# bat_charging.net
KiCad netlist of a schematic drawn in Altium Designer
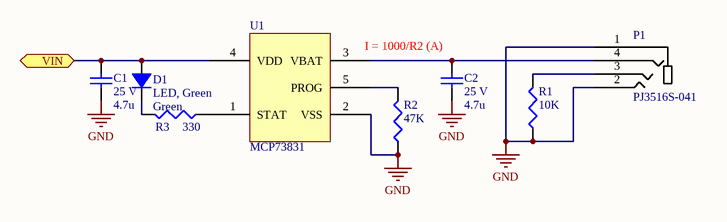
[diagram p0: bat_charging.SchDoc]

(export (version "E")
  (design (tool "Eeschema 10.0.6"))
  (components
    (comp (ref "C1")
      (value "4.7u")
      (footprint "0805")
      (description "Ceramic capacitor, 4.7 uF, 25 V, 0805 package")
      (fields
        (field (name "TOLERANCE") "10%")
        (field (name "VOLTAGE RATED") "25 V")
        (field (name "Comment") "Ceramic capacitor")
      )
      (libsource (lib "rlc") (part "C_4.7u_25V_0805_ceramic"))
    )
    (comp (ref "C2")
      (value "4.7u")
      (footprint "0805")
      (description "Ceramic capacitor, 4.7 uF, 25 V, 0805 package")
      (fields
        (field (name "TOLERANCE") "10%")
        (field (name "VOLTAGE RATED") "25 V")
        (field (name "Comment") "Ceramic capacitor")
      )
      (libsource (lib "rlc") (part "C_4.7u_25V_0805_ceramic"))
    )
    (comp (ref "D1")
      (value "LED, Green")
      (footprint "0603 - LED")
      (description "LED, Green,  0603")
      (fields (field (name "COLOR") "Green"))
      (libsource (lib "rlc") (part "D_LED_GREEN_0603"))
    )
    (comp (ref "P1")
      (value "PJ3516S-041")
      (footprint "PJ3516S-041")
      (description "3.5 mm phone jack, 4 terminals")
      (libsource (lib "connectors") (part "PJ3516S-041"))
    )
    (comp (ref "R1")
      (value "10K")
      (footprint "0603")
      (description "Chip resistor, 10K, 0603 package")
      (fields (field (name "TOLERANCE") "1%") (field (name "POWER") "1/10 W"))
      (libsource (lib "rlc") (part "R_10K_0603"))
    )
    (comp (ref "R2")
      (value "47K")
      (footprint "0603")
      (description "Chip resistor, 47K, 0603 package")
      (fields (field (name "TOLERANCE") "1%") (field (name "POWER") "1/10 W"))
      (libsource (lib "rlc") (part "R_47K_0603"))
    )
    (comp (ref "R3")
      (value "330")
      (footprint "0603")
      (description "Chip resistor, 330, 0603 package")
      (fields (field (name "TOLERANCE") "1%") (field (name "POWER") "1/10 W"))
      (libsource (lib "rlc") (part "R_330_0603"))
    )
    (comp (ref "U1")
      (value "MCP73831")
      (footprint "TSOT23-5")
      (description "Miniature Single-Cell, Fully Integrated Li-Ion,  Li-Polymer Charge Management Controllers")
      (libsource (lib "battery_charging") (part "MCP73831"))
    )
  )
  (nets
    (net (code "1") (name "/VIN") (class "Default")
      (node (ref "C1") (pin "1") (pintype "passive"))
      (node (ref "D1") (pin "1") (pintype "passive"))
      (node (ref "U1") (pin "4") (pinfunction "VDD_4") (pintype "passive"))
    )
    (net (code "2") (name "GND") (class "Default")
      (node (ref "C1") (pin "2") (pintype "passive"))
      (node (ref "C2") (pin "2") (pintype "passive"))
      (node (ref "P1") (pin "1") (pinfunction "1_1") (pintype "passive"))
      (node (ref "P1") (pin "2") (pinfunction "2_2") (pintype "passive"))
      (node (ref "R1") (pin "2") (pintype "passive"))
      (node (ref "R2") (pin "2") (pintype "passive"))
      (node (ref "U1") (pin "2") (pinfunction "VSS_2") (pintype "passive"))
    )
    (net (code "3") (name "Net-(D1-Pad2)") (class "Default")
      (node (ref "D1") (pin "2") (pintype "passive"))
      (node (ref "R3") (pin "1") (pintype "passive"))
    )
    (net (code "4") (name "Net-(P1-Pad3)") (class "Default")
      (node (ref "P1") (pin "3") (pinfunction "3_3") (pintype "passive"))
      (node (ref "R1") (pin "1") (pintype "passive"))
    )
    (net (code "5") (name "Net-(U1-PROG)") (class "Default")
      (node (ref "R2") (pin "1") (pintype "passive"))
      (node (ref "U1") (pin "5") (pinfunction "PROG_5") (pintype "passive"))
    )
    (net (code "6") (name "Net-(U1-STAT)") (class "Default")
      (node (ref "R3") (pin "2") (pintype "passive"))
      (node (ref "U1") (pin "1") (pinfunction "STAT_1") (pintype "passive"))
    )
    (net (code "7") (name "Net-(U1-VBAT)") (class "Default")
      (node (ref "C2") (pin "1") (pintype "passive"))
      (node (ref "P1") (pin "4") (pinfunction "4_4") (pintype "passive"))
      (node (ref "U1") (pin "3") (pinfunction "VBAT_3") (pintype "passive"))
    )
  )
)
